# Keypad_4x4.net
KiCad netlist of a schematic drawn in EAGLE
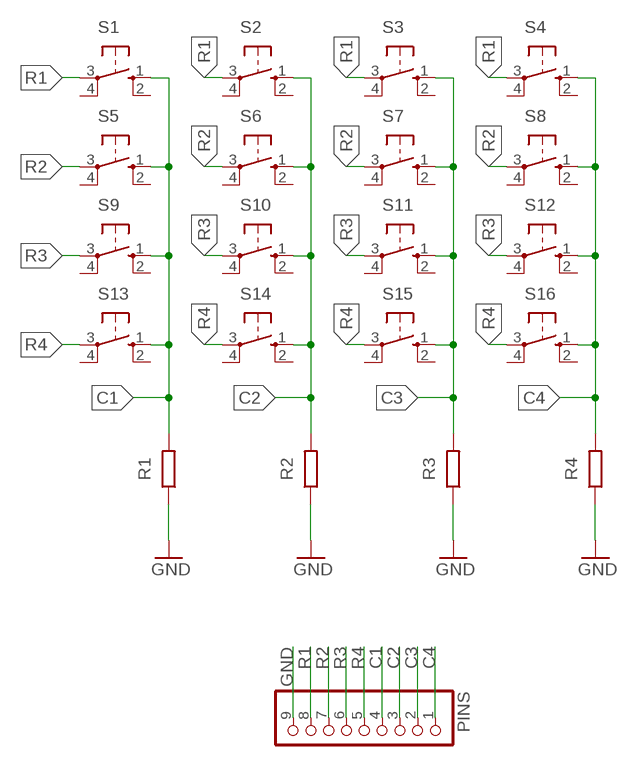
[diagram p0: schematic, sheet 1]

(export (version "E")
  (design (tool "Eeschema 10.0.6"))
  (components
    (comp (ref "PINS")
      (value "PINHD-1X9/90")
      (footprint "eagle-import:1X09_90")
      (libsource (lib "eagle-import") (part "PINHD-1X9/90"))
    )
    (comp (ref "R1")
      (value "100k")
      (footprint "eagle-import:0204_7")
      (libsource (lib "eagle-import") (part "R-EU_0204/7"))
    )
    (comp (ref "R2")
      (value "100k")
      (footprint "eagle-import:0204_7")
      (libsource (lib "eagle-import") (part "R-EU_0204/7"))
    )
    (comp (ref "R3")
      (value "100k")
      (footprint "eagle-import:0204_7")
      (libsource (lib "eagle-import") (part "R-EU_0204/7"))
    )
    (comp (ref "R4")
      (value "100k")
      (footprint "eagle-import:0204_7")
      (libsource (lib "eagle-import") (part "R-EU_0204/7"))
    )
    (comp (ref "S1")
      (value "10-XX")
      (footprint "eagle-import:B3F-10XX")
      (fields (field (name "MPN") "B3F-1000"))
      (libsource (lib "eagle-import") (part "10-XX"))
    )
    (comp (ref "S2")
      (value "10-XX")
      (footprint "eagle-import:B3F-10XX")
      (fields (field (name "MPN") "B3F-1000"))
      (libsource (lib "eagle-import") (part "10-XX"))
    )
    (comp (ref "S3")
      (value "10-XX")
      (footprint "eagle-import:B3F-10XX")
      (fields (field (name "MPN") "B3F-1000"))
      (libsource (lib "eagle-import") (part "10-XX"))
    )
    (comp (ref "S4")
      (value "10-XX")
      (footprint "eagle-import:B3F-10XX")
      (fields (field (name "MPN") "B3F-1000"))
      (libsource (lib "eagle-import") (part "10-XX"))
    )
    (comp (ref "S5")
      (value "10-XX")
      (footprint "eagle-import:B3F-10XX")
      (fields (field (name "MPN") "B3F-1000"))
      (libsource (lib "eagle-import") (part "10-XX"))
    )
    (comp (ref "S6")
      (value "10-XX")
      (footprint "eagle-import:B3F-10XX")
      (fields (field (name "MPN") "B3F-1000"))
      (libsource (lib "eagle-import") (part "10-XX"))
    )
    (comp (ref "S7")
      (value "10-XX")
      (footprint "eagle-import:B3F-10XX")
      (fields (field (name "MPN") "B3F-1000"))
      (libsource (lib "eagle-import") (part "10-XX"))
    )
    (comp (ref "S8")
      (value "10-XX")
      (footprint "eagle-import:B3F-10XX")
      (fields (field (name "MPN") "B3F-1000"))
      (libsource (lib "eagle-import") (part "10-XX"))
    )
    (comp (ref "S9")
      (value "10-XX")
      (footprint "eagle-import:B3F-10XX")
      (fields (field (name "MPN") "B3F-1000"))
      (libsource (lib "eagle-import") (part "10-XX"))
    )
    (comp (ref "S10")
      (value "10-XX")
      (footprint "eagle-import:B3F-10XX")
      (fields (field (name "MPN") "B3F-1000"))
      (libsource (lib "eagle-import") (part "10-XX"))
    )
    (comp (ref "S11")
      (value "10-XX")
      (footprint "eagle-import:B3F-10XX")
      (fields (field (name "MPN") "B3F-1000"))
      (libsource (lib "eagle-import") (part "10-XX"))
    )
    (comp (ref "S12")
      (value "10-XX")
      (footprint "eagle-import:B3F-10XX")
      (fields (field (name "MPN") "B3F-1000"))
      (libsource (lib "eagle-import") (part "10-XX"))
    )
    (comp (ref "S13")
      (value "10-XX")
      (footprint "eagle-import:B3F-10XX")
      (fields (field (name "MPN") "B3F-1000"))
      (libsource (lib "eagle-import") (part "10-XX"))
    )
    (comp (ref "S14")
      (value "10-XX")
      (footprint "eagle-import:B3F-10XX")
      (fields (field (name "MPN") "B3F-1000"))
      (libsource (lib "eagle-import") (part "10-XX"))
    )
    (comp (ref "S15")
      (value "10-XX")
      (footprint "eagle-import:B3F-10XX")
      (fields (field (name "MPN") "B3F-1000"))
      (libsource (lib "eagle-import") (part "10-XX"))
    )
    (comp (ref "S16")
      (value "10-XX")
      (footprint "eagle-import:B3F-10XX")
      (fields (field (name "MPN") "B3F-1000"))
      (libsource (lib "eagle-import") (part "10-XX"))
    )
  )
  (nets
    (net (code "1") (name "C1") (class "Default")
      (node (ref "PINS") (pin "4") (pinfunction "4_4") (pintype "passive"))
      (node (ref "R1") (pin "2") (pinfunction "2_2") (pintype "passive"))
      (node (ref "S1") (pin "1") (pinfunction "S_1") (pintype "passive"))
      (node (ref "S13") (pin "1") (pinfunction "S_1") (pintype "passive"))
      (node (ref "S5") (pin "1") (pinfunction "S_1") (pintype "passive"))
      (node (ref "S9") (pin "1") (pinfunction "S_1") (pintype "passive"))
    )
    (net (code "2") (name "C2") (class "Default")
      (node (ref "PINS") (pin "3") (pinfunction "3_3") (pintype "passive"))
      (node (ref "R2") (pin "2") (pinfunction "2_2") (pintype "passive"))
      (node (ref "S10") (pin "1") (pinfunction "S_1") (pintype "passive"))
      (node (ref "S14") (pin "1") (pinfunction "S_1") (pintype "passive"))
      (node (ref "S2") (pin "1") (pinfunction "S_1") (pintype "passive"))
      (node (ref "S6") (pin "1") (pinfunction "S_1") (pintype "passive"))
    )
    (net (code "3") (name "C3") (class "Default")
      (node (ref "PINS") (pin "2") (pinfunction "2_2") (pintype "passive"))
      (node (ref "R3") (pin "2") (pinfunction "2_2") (pintype "passive"))
      (node (ref "S11") (pin "1") (pinfunction "S_1") (pintype "passive"))
      (node (ref "S15") (pin "1") (pinfunction "S_1") (pintype "passive"))
      (node (ref "S3") (pin "1") (pinfunction "S_1") (pintype "passive"))
      (node (ref "S7") (pin "1") (pinfunction "S_1") (pintype "passive"))
    )
    (net (code "4") (name "C4") (class "Default")
      (node (ref "PINS") (pin "1") (pinfunction "1_1") (pintype "passive"))
      (node (ref "R4") (pin "2") (pinfunction "2_2") (pintype "passive"))
      (node (ref "S12") (pin "1") (pinfunction "S_1") (pintype "passive"))
      (node (ref "S16") (pin "1") (pinfunction "S_1") (pintype "passive"))
      (node (ref "S4") (pin "1") (pinfunction "S_1") (pintype "passive"))
      (node (ref "S8") (pin "1") (pinfunction "S_1") (pintype "passive"))
    )
    (net (code "5") (name "GND") (class "Default")
      (node (ref "PINS") (pin "9") (pinfunction "9_9") (pintype "passive"))
      (node (ref "R1") (pin "1") (pinfunction "1_1") (pintype "passive"))
      (node (ref "R2") (pin "1") (pinfunction "1_1") (pintype "passive"))
      (node (ref "R3") (pin "1") (pinfunction "1_1") (pintype "passive"))
      (node (ref "R4") (pin "1") (pinfunction "1_1") (pintype "passive"))
    )
    (net (code "6") (name "R1") (class "Default")
      (node (ref "PINS") (pin "8") (pinfunction "8_8") (pintype "passive"))
      (node (ref "S1") (pin "3") (pinfunction "P_3") (pintype "passive"))
      (node (ref "S2") (pin "3") (pinfunction "P_3") (pintype "passive"))
      (node (ref "S3") (pin "3") (pinfunction "P_3") (pintype "passive"))
      (node (ref "S4") (pin "3") (pinfunction "P_3") (pintype "passive"))
    )
    (net (code "7") (name "R2") (class "Default")
      (node (ref "PINS") (pin "7") (pinfunction "7_7") (pintype "passive"))
      (node (ref "S5") (pin "3") (pinfunction "P_3") (pintype "passive"))
      (node (ref "S6") (pin "3") (pinfunction "P_3") (pintype "passive"))
      (node (ref "S7") (pin "3") (pinfunction "P_3") (pintype "passive"))
      (node (ref "S8") (pin "3") (pinfunction "P_3") (pintype "passive"))
    )
    (net (code "8") (name "R3") (class "Default")
      (node (ref "PINS") (pin "6") (pinfunction "6_6") (pintype "passive"))
      (node (ref "S10") (pin "3") (pinfunction "P_3") (pintype "passive"))
      (node (ref "S11") (pin "3") (pinfunction "P_3") (pintype "passive"))
      (node (ref "S12") (pin "3") (pinfunction "P_3") (pintype "passive"))
      (node (ref "S9") (pin "3") (pinfunction "P_3") (pintype "passive"))
    )
    (net (code "9") (name "R4") (class "Default")
      (node (ref "PINS") (pin "5") (pinfunction "5_5") (pintype "passive"))
      (node (ref "S13") (pin "3") (pinfunction "P_3") (pintype "passive"))
      (node (ref "S14") (pin "3") (pinfunction "P_3") (pintype "passive"))
      (node (ref "S15") (pin "3") (pinfunction "P_3") (pintype "passive"))
      (node (ref "S16") (pin "3") (pinfunction "P_3") (pintype "passive"))
    )
    (net (code "10") (name "unconnected-(S1-P1-Pad4)") (class "Default")
      (node (ref "S1") (pin "4") (pinfunction "P1_4") (pintype "passive"))
    )
    (net (code "11") (name "unconnected-(S1-S1-Pad2)") (class "Default")
      (node (ref "S1") (pin "2") (pinfunction "S1_2") (pintype "passive"))
    )
    (net (code "12") (name "unconnected-(S2-P1-Pad4)") (class "Default")
      (node (ref "S2") (pin "4") (pinfunction "P1_4") (pintype "passive"))
    )
    (net (code "13") (name "unconnected-(S2-S1-Pad2)") (class "Default")
      (node (ref "S2") (pin "2") (pinfunction "S1_2") (pintype "passive"))
    )
    (net (code "14") (name "unconnected-(S3-P1-Pad4)") (class "Default")
      (node (ref "S3") (pin "4") (pinfunction "P1_4") (pintype "passive"))
    )
    (net (code "15") (name "unconnected-(S3-S1-Pad2)") (class "Default")
      (node (ref "S3") (pin "2") (pinfunction "S1_2") (pintype "passive"))
    )
    (net (code "16") (name "unconnected-(S4-P1-Pad4)") (class "Default")
      (node (ref "S4") (pin "4") (pinfunction "P1_4") (pintype "passive"))
    )
    (net (code "17") (name "unconnected-(S4-S1-Pad2)") (class "Default")
      (node (ref "S4") (pin "2") (pinfunction "S1_2") (pintype "passive"))
    )
    (net (code "18") (name "unconnected-(S5-P1-Pad4)") (class "Default")
      (node (ref "S5") (pin "4") (pinfunction "P1_4") (pintype "passive"))
    )
    (net (code "19") (name "unconnected-(S5-S1-Pad2)") (class "Default")
      (node (ref "S5") (pin "2") (pinfunction "S1_2") (pintype "passive"))
    )
    (net (code "20") (name "unconnected-(S6-P1-Pad4)") (class "Default")
      (node (ref "S6") (pin "4") (pinfunction "P1_4") (pintype "passive"))
    )
    (net (code "21") (name "unconnected-(S6-S1-Pad2)") (class "Default")
      (node (ref "S6") (pin "2") (pinfunction "S1_2") (pintype "passive"))
    )
    (net (code "22") (name "unconnected-(S7-P1-Pad4)") (class "Default")
      (node (ref "S7") (pin "4") (pinfunction "P1_4") (pintype "passive"))
    )
    (net (code "23") (name "unconnected-(S7-S1-Pad2)") (class "Default")
      (node (ref "S7") (pin "2") (pinfunction "S1_2") (pintype "passive"))
    )
    (net (code "24") (name "unconnected-(S8-P1-Pad4)") (class "Default")
      (node (ref "S8") (pin "4") (pinfunction "P1_4") (pintype "passive"))
    )
    (net (code "25") (name "unconnected-(S8-S1-Pad2)") (class "Default")
      (node (ref "S8") (pin "2") (pinfunction "S1_2") (pintype "passive"))
    )
    (net (code "26") (name "unconnected-(S9-P1-Pad4)") (class "Default")
      (node (ref "S9") (pin "4") (pinfunction "P1_4") (pintype "passive"))
    )
    (net (code "27") (name "unconnected-(S9-S1-Pad2)") (class "Default")
      (node (ref "S9") (pin "2") (pinfunction "S1_2") (pintype "passive"))
    )
    (net (code "28") (name "unconnected-(S10-P1-Pad4)") (class "Default")
      (node (ref "S10") (pin "4") (pinfunction "P1_4") (pintype "passive"))
    )
    (net (code "29") (name "unconnected-(S10-S1-Pad2)") (class "Default")
      (node (ref "S10") (pin "2") (pinfunction "S1_2") (pintype "passive"))
    )
    (net (code "30") (name "unconnected-(S11-P1-Pad4)") (class "Default")
      (node (ref "S11") (pin "4") (pinfunction "P1_4") (pintype "passive"))
    )
    (net (code "31") (name "unconnected-(S11-S1-Pad2)") (class "Default")
      (node (ref "S11") (pin "2") (pinfunction "S1_2") (pintype "passive"))
    )
    (net (code "32") (name "unconnected-(S12-P1-Pad4)") (class "Default")
      (node (ref "S12") (pin "4") (pinfunction "P1_4") (pintype "passive"))
    )
    (net (code "33") (name "unconnected-(S12-S1-Pad2)") (class "Default")
      (node (ref "S12") (pin "2") (pinfunction "S1_2") (pintype "passive"))
    )
    (net (code "34") (name "unconnected-(S13-P1-Pad4)") (class "Default")
      (node (ref "S13") (pin "4") (pinfunction "P1_4") (pintype "passive"))
    )
    (net (code "35") (name "unconnected-(S13-S1-Pad2)") (class "Default")
      (node (ref "S13") (pin "2") (pinfunction "S1_2") (pintype "passive"))
    )
    (net (code "36") (name "unconnected-(S14-P1-Pad4)") (class "Default")
      (node (ref "S14") (pin "4") (pinfunction "P1_4") (pintype "passive"))
    )
    (net (code "37") (name "unconnected-(S14-S1-Pad2)") (class "Default")
      (node (ref "S14") (pin "2") (pinfunction "S1_2") (pintype "passive"))
    )
    (net (code "38") (name "unconnected-(S15-P1-Pad4)") (class "Default")
      (node (ref "S15") (pin "4") (pinfunction "P1_4") (pintype "passive"))
    )
    (net (code "39") (name "unconnected-(S15-S1-Pad2)") (class "Default")
      (node (ref "S15") (pin "2") (pinfunction "S1_2") (pintype "passive"))
    )
    (net (code "40") (name "unconnected-(S16-P1-Pad4)") (class "Default")
      (node (ref "S16") (pin "4") (pinfunction "P1_4") (pintype "passive"))
    )
    (net (code "41") (name "unconnected-(S16-S1-Pad2)") (class "Default")
      (node (ref "S16") (pin "2") (pinfunction "S1_2") (pintype "passive"))
    )
  )
)
